# ATmega324PA.net
KiCad netlist of a schematic drawn in EAGLE
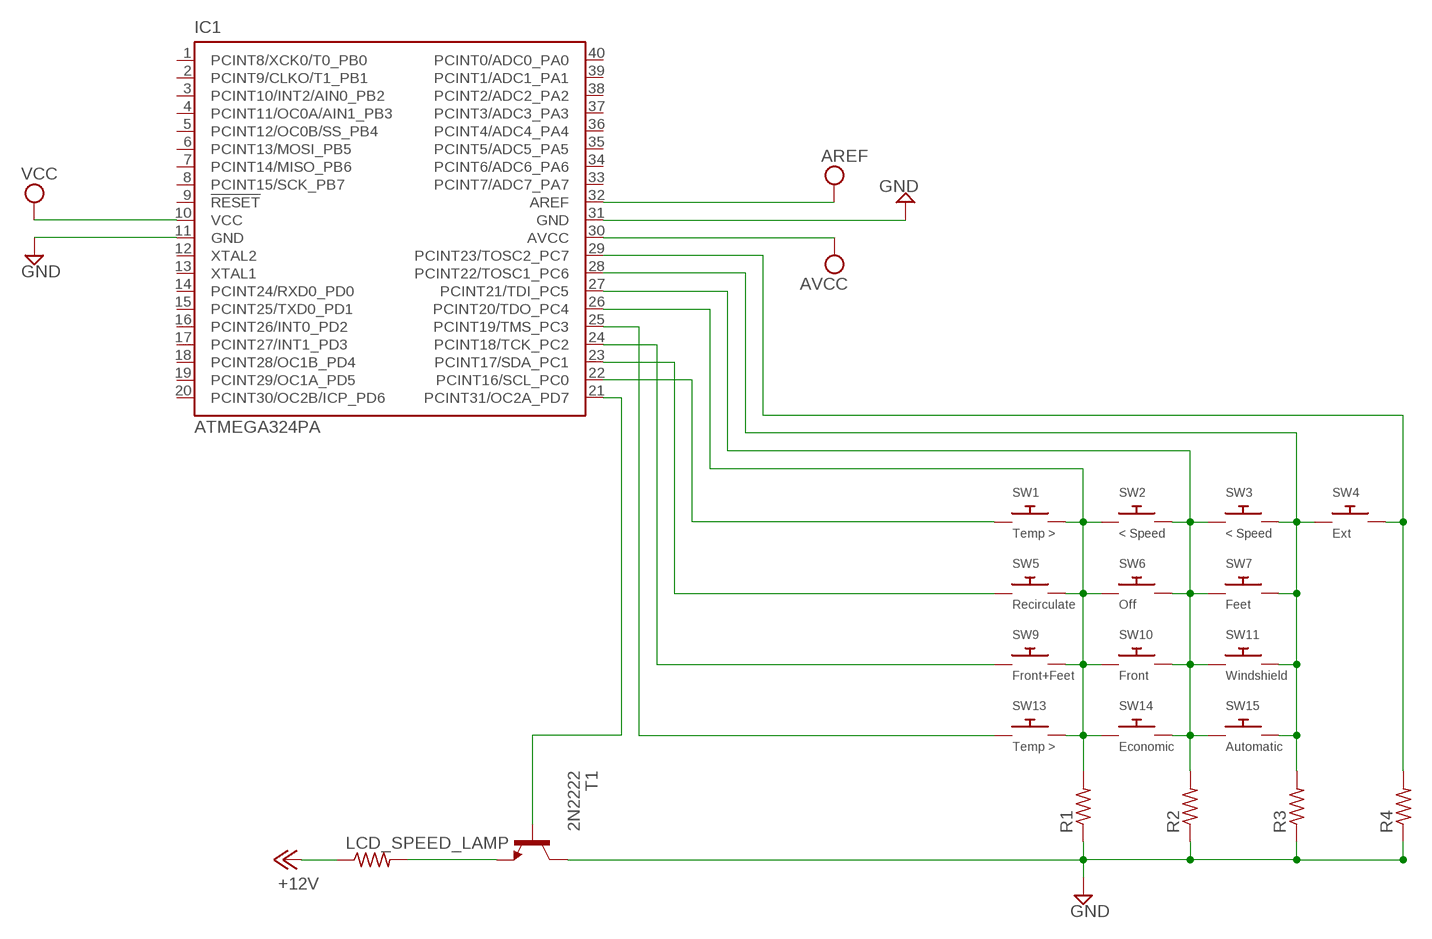
[diagram p0: schematic, sheet 1]

(export (version "E")
  (design (tool "Eeschema 10.0.6"))
  (components
    (comp (ref "IC1")
      (value "ATMEGA324PA")
      (footprint "eagle-import:DIL40")
      (fields (field (name "MPN") "ATMEGA644V-10PU"))
      (libsource (lib "eagle-import") (part "ATMEGA644-PU10"))
    )
    (comp (ref "LCD_SPEED_LAMP")
      (value "R-US_0204/7")
      (footprint "eagle-import:0204_7")
      (libsource (lib "eagle-import") (part "R-US_0204/7"))
    )
    (comp (ref "R1")
      (value "R-US_0204/7")
      (footprint "eagle-import:0204_7")
      (libsource (lib "eagle-import") (part "R-US_0204/7"))
    )
    (comp (ref "R2")
      (value "R-US_0204/7")
      (footprint "eagle-import:0204_7")
      (libsource (lib "eagle-import") (part "R-US_0204/7"))
    )
    (comp (ref "R3")
      (value "R-US_0204/7")
      (footprint "eagle-import:0204_7")
      (libsource (lib "eagle-import") (part "R-US_0204/7"))
    )
    (comp (ref "R4")
      (value "R-US_0204/7")
      (footprint "eagle-import:0204_7")
      (libsource (lib "eagle-import") (part "R-US_0204/7"))
    )
    (comp (ref "SW1")
      (value "Temp >")
      (footprint "eagle-import:BTN_CK_KSS")
      (libsource (lib "eagle-import") (part "SWITCH_PUSHBUTTONC&K_KSS"))
    )
    (comp (ref "SW2")
      (value "< Speed")
      (footprint "eagle-import:BTN_CK_KSS")
      (libsource (lib "eagle-import") (part "SWITCH_PUSHBUTTONC&K_KSS"))
    )
    (comp (ref "SW3")
      (value "< Speed")
      (footprint "eagle-import:BTN_CK_KSS")
      (libsource (lib "eagle-import") (part "SWITCH_PUSHBUTTONC&K_KSS"))
    )
    (comp (ref "SW4")
      (value "Ext")
      (footprint "eagle-import:BTN_CK_KSS")
      (libsource (lib "eagle-import") (part "SWITCH_PUSHBUTTONC&K_KSS"))
    )
    (comp (ref "SW5")
      (value "Recirculate")
      (footprint "eagle-import:BTN_CK_KSS")
      (libsource (lib "eagle-import") (part "SWITCH_PUSHBUTTONC&K_KSS"))
    )
    (comp (ref "SW6")
      (value "Off")
      (footprint "eagle-import:BTN_CK_KSS")
      (libsource (lib "eagle-import") (part "SWITCH_PUSHBUTTONC&K_KSS"))
    )
    (comp (ref "SW7")
      (value "Feet")
      (footprint "eagle-import:BTN_CK_KSS")
      (libsource (lib "eagle-import") (part "SWITCH_PUSHBUTTONC&K_KSS"))
    )
    (comp (ref "SW9")
      (value "Front+Feet")
      (footprint "eagle-import:BTN_CK_KSS")
      (libsource (lib "eagle-import") (part "SWITCH_PUSHBUTTONC&K_KSS"))
    )
    (comp (ref "SW10")
      (value "Front")
      (footprint "eagle-import:BTN_CK_KSS")
      (libsource (lib "eagle-import") (part "SWITCH_PUSHBUTTONC&K_KSS"))
    )
    (comp (ref "SW11")
      (value "Windshield")
      (footprint "eagle-import:BTN_CK_KSS")
      (libsource (lib "eagle-import") (part "SWITCH_PUSHBUTTONC&K_KSS"))
    )
    (comp (ref "SW13")
      (value "Temp >")
      (footprint "eagle-import:BTN_CK_KSS")
      (libsource (lib "eagle-import") (part "SWITCH_PUSHBUTTONC&K_KSS"))
    )
    (comp (ref "SW14")
      (value "Economic")
      (footprint "eagle-import:BTN_CK_KSS")
      (libsource (lib "eagle-import") (part "SWITCH_PUSHBUTTONC&K_KSS"))
    )
    (comp (ref "SW15")
      (value "Automatic")
      (footprint "eagle-import:BTN_CK_KSS")
      (libsource (lib "eagle-import") (part "SWITCH_PUSHBUTTONC&K_KSS"))
    )
    (comp (ref "T1")
      (value "2N2222")
      (footprint "eagle-import:TO92-EBC-OVAL")
      (libsource (lib "eagle-import") (part "2N2222"))
    )
  )
  (nets
    (net (code "1") (name "+12V") (class "Default")
      (node (ref "LCD_SPEED_LAMP") (pin "1") (pinfunction "1_1") (pintype "passive"))
    )
    (net (code "2") (name "AREF") (class "Default")
      (node (ref "IC1") (pin "10") (pinfunction "VCC_10") (pintype "power_in"))
      (node (ref "IC1") (pin "30") (pinfunction "AVCC_30") (pintype "power_in"))
      (node (ref "IC1") (pin "32") (pinfunction "AREF_32") (pintype "passive"))
    )
    (net (code "3") (name "GND") (class "Default")
      (node (ref "IC1") (pin "11") (pinfunction "GND_11") (pintype "power_in"))
      (node (ref "IC1") (pin "31") (pinfunction "GND_31") (pintype "power_in"))
      (node (ref "R1") (pin "1") (pinfunction "1_1") (pintype "passive"))
      (node (ref "R2") (pin "1") (pinfunction "1_1") (pintype "passive"))
      (node (ref "R3") (pin "1") (pinfunction "1_1") (pintype "passive"))
      (node (ref "R4") (pin "1") (pinfunction "1_1") (pintype "passive"))
      (node (ref "T1") (pin "C") (pinfunction "C_C") (pintype "passive"))
    )
    (net (code "4") (name "Net-(IC1-PCINT16{slash}SCL_PC0)") (class "Default")
      (node (ref "IC1") (pin "22") (pinfunction "PCINT16/SCL_PC0_22") (pintype "bidirectional"))
      (node (ref "SW1") (pin "P$1") (pinfunction "P$1_P$1") (pintype "passive"))
    )
    (net (code "5") (name "Net-(IC1-PCINT17{slash}SDA_PC1)") (class "Default")
      (node (ref "IC1") (pin "23") (pinfunction "PCINT17/SDA_PC1_23") (pintype "bidirectional"))
      (node (ref "SW5") (pin "P$1") (pinfunction "P$1_P$1") (pintype "passive"))
    )
    (net (code "6") (name "Net-(IC1-PCINT18{slash}TCK_PC2)") (class "Default")
      (node (ref "IC1") (pin "24") (pinfunction "PCINT18/TCK_PC2_24") (pintype "bidirectional"))
      (node (ref "SW9") (pin "P$1") (pinfunction "P$1_P$1") (pintype "passive"))
    )
    (net (code "7") (name "Net-(IC1-PCINT19{slash}TMS_PC3)") (class "Default")
      (node (ref "IC1") (pin "25") (pinfunction "PCINT19/TMS_PC3_25") (pintype "bidirectional"))
      (node (ref "SW13") (pin "P$1") (pinfunction "P$1_P$1") (pintype "passive"))
    )
    (net (code "8") (name "Net-(IC1-PCINT20{slash}TDO_PC4)") (class "Default")
      (node (ref "IC1") (pin "26") (pinfunction "PCINT20/TDO_PC4_26") (pintype "bidirectional"))
      (node (ref "R1") (pin "2") (pinfunction "2_2") (pintype "passive"))
      (node (ref "SW1") (pin "P$2") (pinfunction "P$2_P$2") (pintype "passive"))
      (node (ref "SW10") (pin "P$1") (pinfunction "P$1_P$1") (pintype "passive"))
      (node (ref "SW13") (pin "P$2") (pinfunction "P$2_P$2") (pintype "passive"))
      (node (ref "SW14") (pin "P$1") (pinfunction "P$1_P$1") (pintype "passive"))
      (node (ref "SW2") (pin "P$1") (pinfunction "P$1_P$1") (pintype "passive"))
      (node (ref "SW5") (pin "P$2") (pinfunction "P$2_P$2") (pintype "passive"))
      (node (ref "SW6") (pin "P$1") (pinfunction "P$1_P$1") (pintype "passive"))
      (node (ref "SW9") (pin "P$2") (pinfunction "P$2_P$2") (pintype "passive"))
    )
    (net (code "9") (name "Net-(IC1-PCINT21{slash}TDI_PC5)") (class "Default")
      (node (ref "IC1") (pin "27") (pinfunction "PCINT21/TDI_PC5_27") (pintype "bidirectional"))
      (node (ref "R2") (pin "2") (pinfunction "2_2") (pintype "passive"))
      (node (ref "SW10") (pin "P$2") (pinfunction "P$2_P$2") (pintype "passive"))
      (node (ref "SW11") (pin "P$1") (pinfunction "P$1_P$1") (pintype "passive"))
      (node (ref "SW14") (pin "P$2") (pinfunction "P$2_P$2") (pintype "passive"))
      (node (ref "SW15") (pin "P$1") (pinfunction "P$1_P$1") (pintype "passive"))
      (node (ref "SW2") (pin "P$2") (pinfunction "P$2_P$2") (pintype "passive"))
      (node (ref "SW3") (pin "P$1") (pinfunction "P$1_P$1") (pintype "passive"))
      (node (ref "SW6") (pin "P$2") (pinfunction "P$2_P$2") (pintype "passive"))
      (node (ref "SW7") (pin "P$1") (pinfunction "P$1_P$1") (pintype "passive"))
    )
    (net (code "10") (name "Net-(IC1-PCINT22{slash}TOSC1_PC6)") (class "Default")
      (node (ref "IC1") (pin "28") (pinfunction "PCINT22/TOSC1_PC6_28") (pintype "bidirectional"))
      (node (ref "R3") (pin "2") (pinfunction "2_2") (pintype "passive"))
      (node (ref "SW11") (pin "P$2") (pinfunction "P$2_P$2") (pintype "passive"))
      (node (ref "SW15") (pin "P$2") (pinfunction "P$2_P$2") (pintype "passive"))
      (node (ref "SW3") (pin "P$2") (pinfunction "P$2_P$2") (pintype "passive"))
      (node (ref "SW4") (pin "P$1") (pinfunction "P$1_P$1") (pintype "passive"))
      (node (ref "SW7") (pin "P$2") (pinfunction "P$2_P$2") (pintype "passive"))
    )
    (net (code "11") (name "Net-(IC1-PCINT23{slash}TOSC2_PC7)") (class "Default")
      (node (ref "IC1") (pin "29") (pinfunction "PCINT23/TOSC2_PC7_29") (pintype "bidirectional"))
      (node (ref "R4") (pin "2") (pinfunction "2_2") (pintype "passive"))
      (node (ref "SW4") (pin "P$2") (pinfunction "P$2_P$2") (pintype "passive"))
    )
    (net (code "12") (name "Net-(IC1-PCINT31{slash}OC2A_PD7)") (class "Default")
      (node (ref "IC1") (pin "21") (pinfunction "PCINT31/OC2A_PD7_21") (pintype "bidirectional"))
      (node (ref "T1") (pin "B") (pinfunction "B_B") (pintype "passive"))
    )
    (net (code "13") (name "Net-(LCD_SPEED_LAMP-Pad2)") (class "Default")
      (node (ref "LCD_SPEED_LAMP") (pin "2") (pinfunction "2_2") (pintype "passive"))
      (node (ref "T1") (pin "E") (pinfunction "E_E") (pintype "passive"))
    )
    (net (code "14") (name "unconnected-(IC1-PCINT0{slash}ADC0_PA0-Pad40)") (class "Default")
      (node (ref "IC1") (pin "40") (pinfunction "PCINT0/ADC0_PA0_40") (pintype "bidirectional"))
    )
    (net (code "15") (name "unconnected-(IC1-PCINT1{slash}ADC1_PA1-Pad39)") (class "Default")
      (node (ref "IC1") (pin "39") (pinfunction "PCINT1/ADC1_PA1_39") (pintype "bidirectional"))
    )
    (net (code "16") (name "unconnected-(IC1-PCINT2{slash}ADC2_PA2-Pad38)") (class "Default")
      (node (ref "IC1") (pin "38") (pinfunction "PCINT2/ADC2_PA2_38") (pintype "bidirectional"))
    )
    (net (code "17") (name "unconnected-(IC1-PCINT3{slash}ADC3_PA3-Pad37)") (class "Default")
      (node (ref "IC1") (pin "37") (pinfunction "PCINT3/ADC3_PA3_37") (pintype "bidirectional"))
    )
    (net (code "18") (name "unconnected-(IC1-PCINT4{slash}ADC4_PA4-Pad36)") (class "Default")
      (node (ref "IC1") (pin "36") (pinfunction "PCINT4/ADC4_PA4_36") (pintype "bidirectional"))
    )
    (net (code "19") (name "unconnected-(IC1-PCINT5{slash}ADC5_PA5-Pad35)") (class "Default")
      (node (ref "IC1") (pin "35") (pinfunction "PCINT5/ADC5_PA5_35") (pintype "bidirectional"))
    )
    (net (code "20") (name "unconnected-(IC1-PCINT6{slash}ADC6_PA6-Pad34)") (class "Default")
      (node (ref "IC1") (pin "34") (pinfunction "PCINT6/ADC6_PA6_34") (pintype "bidirectional"))
    )
    (net (code "21") (name "unconnected-(IC1-PCINT7{slash}ADC7_PA7-Pad33)") (class "Default")
      (node (ref "IC1") (pin "33") (pinfunction "PCINT7/ADC7_PA7_33") (pintype "bidirectional"))
    )
    (net (code "22") (name "unconnected-(IC1-PCINT8{slash}XCK0{slash}T0_PB0-Pad1)") (class "Default")
      (node (ref "IC1") (pin "1") (pinfunction "PCINT8/XCK0/T0_PB0_1") (pintype "bidirectional"))
    )
    (net (code "23") (name "unconnected-(IC1-PCINT9{slash}CLKO{slash}T1_PB1-Pad2)") (class "Default")
      (node (ref "IC1") (pin "2") (pinfunction "PCINT9/CLKO/T1_PB1_2") (pintype "bidirectional"))
    )
    (net (code "24") (name "unconnected-(IC1-PCINT10{slash}INT2{slash}AIN0_PB2-Pad3)") (class "Default")
      (node (ref "IC1") (pin "3") (pinfunction "PCINT10/INT2/AIN0_PB2_3") (pintype "bidirectional"))
    )
    (net (code "25") (name "unconnected-(IC1-PCINT11{slash}OC0A{slash}AIN1_PB3-Pad4)") (class "Default")
      (node (ref "IC1") (pin "4") (pinfunction "PCINT11/OC0A/AIN1_PB3_4") (pintype "bidirectional"))
    )
    (net (code "26") (name "unconnected-(IC1-PCINT12{slash}OC0B{slash}SS_PB4-Pad5)") (class "Default")
      (node (ref "IC1") (pin "5") (pinfunction "PCINT12/OC0B/SS_PB4_5") (pintype "bidirectional"))
    )
    (net (code "27") (name "unconnected-(IC1-PCINT13{slash}MOSI_PB5-Pad6)") (class "Default")
      (node (ref "IC1") (pin "6") (pinfunction "PCINT13/MOSI_PB5_6") (pintype "bidirectional"))
    )
    (net (code "28") (name "unconnected-(IC1-PCINT14{slash}MISO_PB6-Pad7)") (class "Default")
      (node (ref "IC1") (pin "7") (pinfunction "PCINT14/MISO_PB6_7") (pintype "bidirectional"))
    )
    (net (code "29") (name "unconnected-(IC1-PCINT15{slash}SCK_PB7-Pad8)") (class "Default")
      (node (ref "IC1") (pin "8") (pinfunction "PCINT15/SCK_PB7_8") (pintype "bidirectional"))
    )
    (net (code "30") (name "unconnected-(IC1-PCINT24{slash}RXD0_PD0-Pad14)") (class "Default")
      (node (ref "IC1") (pin "14") (pinfunction "PCINT24/RXD0_PD0_14") (pintype "bidirectional"))
    )
    (net (code "31") (name "unconnected-(IC1-PCINT25{slash}TXD0_PD1-Pad15)") (class "Default")
      (node (ref "IC1") (pin "15") (pinfunction "PCINT25/TXD0_PD1_15") (pintype "bidirectional"))
    )
    (net (code "32") (name "unconnected-(IC1-PCINT26{slash}INT0_PD2-Pad16)") (class "Default")
      (node (ref "IC1") (pin "16") (pinfunction "PCINT26/INT0_PD2_16") (pintype "bidirectional"))
    )
    (net (code "33") (name "unconnected-(IC1-PCINT27{slash}INT1_PD3-Pad17)") (class "Default")
      (node (ref "IC1") (pin "17") (pinfunction "PCINT27/INT1_PD3_17") (pintype "bidirectional"))
    )
    (net (code "34") (name "unconnected-(IC1-PCINT28{slash}OC1B_PD4-Pad18)") (class "Default")
      (node (ref "IC1") (pin "18") (pinfunction "PCINT28/OC1B_PD4_18") (pintype "bidirectional"))
    )
    (net (code "35") (name "unconnected-(IC1-PCINT29{slash}OC1A_PD5-Pad19)") (class "Default")
      (node (ref "IC1") (pin "19") (pinfunction "PCINT29/OC1A_PD5_19") (pintype "bidirectional"))
    )
    (net (code "36") (name "unconnected-(IC1-PCINT30{slash}OC2B{slash}ICP_PD6-Pad20)") (class "Default")
      (node (ref "IC1") (pin "20") (pinfunction "PCINT30/OC2B/ICP_PD6_20") (pintype "bidirectional"))
    )
    (net (code "37") (name "unconnected-(IC1-XTAL1-Pad13)") (class "Default")
      (node (ref "IC1") (pin "13") (pinfunction "XTAL1_13") (pintype "input"))
    )
    (net (code "38") (name "unconnected-(IC1-XTAL2-Pad12)") (class "Default")
      (node (ref "IC1") (pin "12") (pinfunction "XTAL2_12") (pintype "output"))
    )
    (net (code "39") (name "unconnected-(IC1-~{RESET}-Pad9)") (class "Default")
      (node (ref "IC1") (pin "9") (pinfunction "~{RESET}_9") (pintype "input"))
    )
  )
)
